# 5_Ethernet.net
KiCad netlist of a schematic drawn in Altium Designer
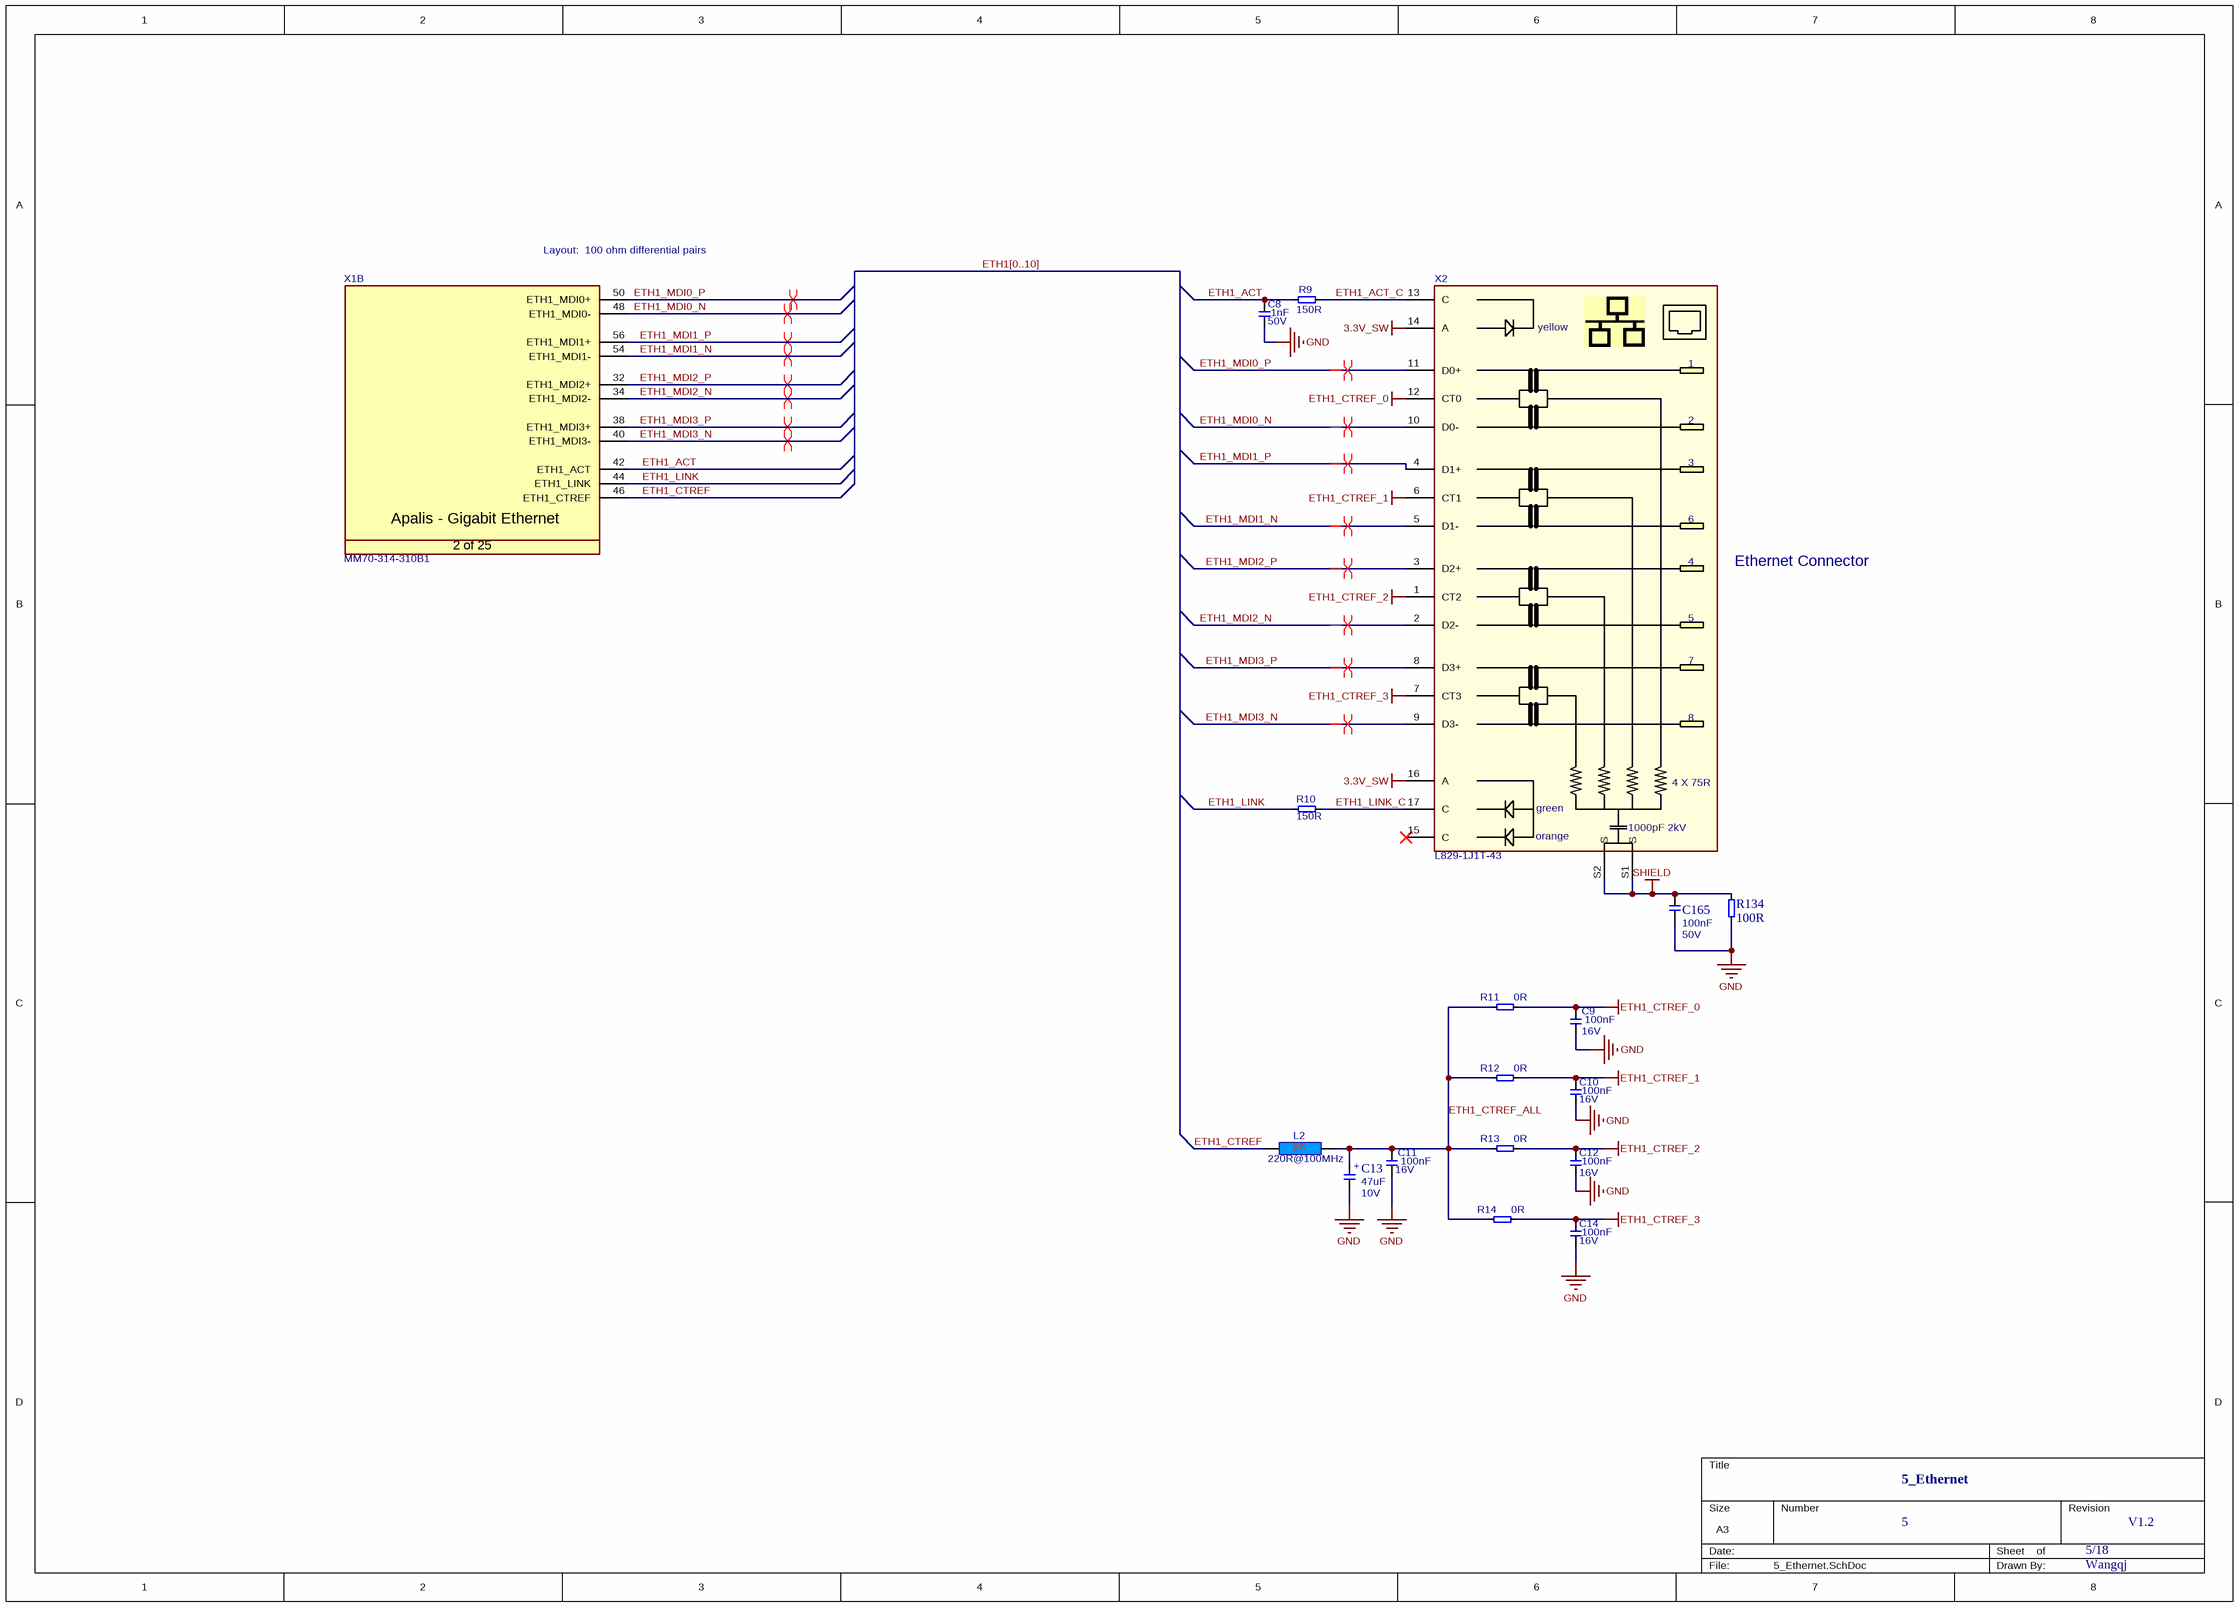
[diagram p0: 5_Ethernet.SchDoc]

(export (version "E")
  (design (tool "Eeschema 10.0.6"))
  (components
    (comp (ref "C8")
      (value "1nF")
      (footprint "CAPC1005X60N")
      (description "Capacitor Ceramic X7R 1nF 50V 10% 0402")
      (fields (field (name "TOLERANCE") "10%") (field (name "RATING") "50V"))
      (libsource (lib "Apalis Evaluation Board") (part "C-X7R-1nF-50V-10%-0402"))
    )
    (comp (ref "C9")
      (value "100nF")
      (footprint "T_CAPC0603X33N")
      (description "Capacitor Ceramic X7R 100nF 16V 10% 0603")
      (fields (field (name "TOLERANCE") "10%") (field (name "RATING") "16V"))
      (libsource (lib "Apalis Evaluation Board") (part "C-X7R-100nF-16V-10%-0603"))
    )
    (comp (ref "C10")
      (value "100nF")
      (footprint "T_CAPC0603X33N")
      (description "Capacitor Ceramic X7R 100nF 16V 10% 0603")
      (fields (field (name "TOLERANCE") "10%") (field (name "RATING") "16V"))
      (libsource (lib "Apalis Evaluation Board") (part "C-X7R-100nF-16V-10%-0603"))
    )
    (comp (ref "C11")
      (value "100nF")
      (footprint "T_CAPC0603X33N")
      (description "Capacitor Ceramic X7R 100nF 16V 10% 0603")
      (fields (field (name "TOLERANCE") "10%") (field (name "RATING") "16V"))
      (libsource (lib "Apalis Evaluation Board") (part "C-X7R-100nF-16V-10%-0603"))
    )
    (comp (ref "C12")
      (value "100nF")
      (footprint "T_CAPC0603X33N")
      (description "Capacitor Ceramic X7R 100nF 16V 10% 0603")
      (fields (field (name "TOLERANCE") "10%") (field (name "RATING") "16V"))
      (libsource (lib "Apalis Evaluation Board") (part "C-X7R-100nF-16V-10%-0603"))
    )
    (comp (ref "C13")
      (value "47uF")
      (footprint "T_CAPMP3216X180N")
      (description "Capacitor TA 47uF 10V 10% 3216")
      (fields (field (name "TOLERANCE") "10%") (field (name "RATING") "10V"))
      (libsource (lib "Apalis Evaluation Board") (part "C-47uF-10V-10%-3216-TA"))
    )
    (comp (ref "C14")
      (value "100nF")
      (footprint "T_CAPC0603X33N")
      (description "Capacitor Ceramic X7R 100nF 16V 10% 0603")
      (fields (field (name "TOLERANCE") "10%") (field (name "RATING") "16V"))
      (libsource (lib "Apalis Evaluation Board") (part "C-X7R-100nF-16V-10%-0603"))
    )
    (comp (ref "C165")
      (value "100nF")
      (footprint "T_CAPC0603X33N")
      (description "Capacitor Ceramic X7R 100nF 50V 20% 0603")
      (fields (field (name "TOLERANCE") "20%") (field (name "RATING") "50V"))
      (libsource (lib "Apalis Evaluation Board") (part "C-100nF-50V-20%-0603-X7R"))
    )
    (comp (ref "L2")
      (value "220R@100MHz")
      (footprint "INDC1608X95N")
      (description "220R@100MHz 2A EMI FILTER")
      (fields (field (name "TOLERANCE") "25%"))
      (libsource (lib "Apalis Evaluation Board") (part "L-220R@100MHz-2A-25%-0603"))
    )
    (comp (ref "R9")
      (value "150R")
      (footprint "t_RESC0603X30N")
      (description "Resistor 150 ohm 63mW 1% 0603")
      (fields (field (name "TOLERANCE") "1%"))
      (libsource (lib "Apalis Evaluation Board") (part "R-150R-63mW-1%-0603"))
    )
    (comp (ref "R10")
      (value "150R")
      (footprint "t_RESC0603X30N")
      (description "Resistor 150 ohm 63mW 1% 0603")
      (fields (field (name "TOLERANCE") "1%"))
      (libsource (lib "Apalis Evaluation Board") (part "R-150R-63mW-1%-0603"))
    )
    (comp (ref "R11")
      (value "0R")
      (footprint "T_RESC0603X30N")
      (description "Resistor 0 ohm 63mW 1% 0603")
      (fields (field (name "TOLERANCE") "1%"))
      (libsource (lib "Apalis Evaluation Board") (part "R-0R-63mW-1%-0603"))
    )
    (comp (ref "R12")
      (value "0R")
      (footprint "T_RESC0603X30N")
      (description "Resistor 0 ohm 63mW 1% 0603")
      (fields (field (name "TOLERANCE") "1%"))
      (libsource (lib "Apalis Evaluation Board") (part "R-0R-63mW-1%-0603"))
    )
    (comp (ref "R13")
      (value "0R")
      (footprint "T_RESC0603X30N")
      (description "Resistor 0 ohm 63mW 1% 0603")
      (fields (field (name "TOLERANCE") "1%"))
      (libsource (lib "Apalis Evaluation Board") (part "R-0R-63mW-1%-0603"))
    )
    (comp (ref "R14")
      (value "0R")
      (footprint "T_RESC0603X30N")
      (description "Resistor 0 ohm 63mW 1% 0603")
      (fields (field (name "TOLERANCE") "1%"))
      (libsource (lib "Apalis Evaluation Board") (part "R-0R-63mW-1%-0603"))
    )
    (comp (ref "R134")
      (value "100R")
      (footprint "T_RESC0603X30N")
      (description "Resistor 120 ohm 63mW 5% 0603")
      (fields (field (name "TOLERANCE") "5%"))
      (libsource (lib "Apalis Evaluation Board") (part "R-120R-63mW-5%-0603"))
    )
    (comp (ref "X1")
      (value "CON-JAE-MM70-314-310B1-314-0.5mm")
      (footprint "T_JAE_MM70-314-310B1")
      (description "MXM3 Connector")
      (fields (field (name "MANUFACTURER PART NO.") "MM70-314-310B1"))
      (libsource (lib "Apalis Evaluation Board") (part "CON-JAE-MM70-314-310B1-314-0.5mm"))
    )
    (comp (ref "X2")
      (value "L829-1J1T-43")
      (footprint "T_BEL_L829-1J1T-43")
      (description "Low profile 10/100/1G Mag Jack")
      (fields (field (name "MANUFACTURER PART NO.") "L829-1J1T-43"))
      (libsource (lib "Apalis Evaluation Board") (part "CON-BEL-L829-1J1T-43"))
    )
  )
  (nets
    (net (code "13") (name "/ETH1_ACT") (class "Default")
      (node (ref "C8") (pin "2") (pinfunction "2_2") (pintype "passive"))
      (node (ref "R9") (pin "1") (pinfunction "1_1") (pintype "passive"))
      (node (ref "X1") (pin "42") (pinfunction "ETH1_ACT_42") (pintype "passive"))
    )
    (net (code "14") (name "/ETH1_ACT_C") (class "Default")
      (node (ref "R9") (pin "2") (pinfunction "2_2") (pintype "passive"))
      (node (ref "X2") (pin "13") (pinfunction "C_13") (pintype "passive"))
    )
    (net (code "15") (name "/ETH1_CTREF") (class "Default")
      (node (ref "L2") (pin "1") (pinfunction "1_1") (pintype "passive"))
      (node (ref "X1") (pin "46") (pinfunction "ETH1_CTREF_46") (pintype "passive"))
    )
    (net (code "16") (name "/ETH1_CTREF_ALL") (class "Default")
      (node (ref "C11") (pin "2") (pinfunction "2_2") (pintype "passive"))
      (node (ref "C13") (pin "1") (pinfunction "1_1") (pintype "passive"))
      (node (ref "L2") (pin "2") (pinfunction "2_2") (pintype "passive"))
      (node (ref "R11") (pin "1") (pinfunction "1_1") (pintype "passive"))
      (node (ref "R12") (pin "1") (pinfunction "1_1") (pintype "passive"))
      (node (ref "R13") (pin "1") (pinfunction "1_1") (pintype "passive"))
      (node (ref "R14") (pin "1") (pinfunction "1_1") (pintype "passive"))
    )
    (net (code "17") (name "/ETH1_LINK") (class "Default")
      (node (ref "R10") (pin "1") (pinfunction "1_1") (pintype "passive"))
      (node (ref "X1") (pin "44") (pinfunction "ETH1_LINK_44") (pintype "passive"))
    )
    (net (code "18") (name "/ETH1_LINK_C") (class "Default")
      (node (ref "R10") (pin "2") (pinfunction "2_2") (pintype "passive"))
      (node (ref "X2") (pin "17") (pinfunction "C_17") (pintype "passive"))
    )
    (net (code "19") (name "/ETH1_MDI0_N") (class "Default")
      (node (ref "X1") (pin "48") (pinfunction "ETH1_MDI0-_48") (pintype "passive"))
      (node (ref "X2") (pin "10") (pinfunction "D0-_10") (pintype "passive"))
    )
    (net (code "20") (name "/ETH1_MDI0_P") (class "Default")
      (node (ref "X1") (pin "50") (pinfunction "ETH1_MDI0+_50") (pintype "passive"))
      (node (ref "X2") (pin "11") (pinfunction "D0+_11") (pintype "passive"))
    )
    (net (code "21") (name "/ETH1_MDI1_N") (class "Default")
      (node (ref "X1") (pin "54") (pinfunction "ETH1_MDI1-_54") (pintype "passive"))
      (node (ref "X2") (pin "5") (pinfunction "D1-_5") (pintype "passive"))
    )
    (net (code "22") (name "/ETH1_MDI1_P") (class "Default")
      (node (ref "X1") (pin "56") (pinfunction "ETH1_MDI1+_56") (pintype "passive"))
      (node (ref "X2") (pin "4") (pinfunction "D1+_4") (pintype "passive"))
    )
    (net (code "23") (name "/ETH1_MDI2_N") (class "Default")
      (node (ref "X1") (pin "34") (pinfunction "ETH1_MDI2-_34") (pintype "passive"))
      (node (ref "X2") (pin "2") (pinfunction "D2-_2") (pintype "passive"))
    )
    (net (code "24") (name "/ETH1_MDI2_P") (class "Default")
      (node (ref "X1") (pin "32") (pinfunction "ETH1_MDI2+_32") (pintype "passive"))
      (node (ref "X2") (pin "3") (pinfunction "D2+_3") (pintype "passive"))
    )
    (net (code "25") (name "/ETH1_MDI3_N") (class "Default")
      (node (ref "X1") (pin "40") (pinfunction "ETH1_MDI3-_40") (pintype "passive"))
      (node (ref "X2") (pin "9") (pinfunction "D3-_9") (pintype "passive"))
    )
    (net (code "26") (name "/ETH1_MDI3_P") (class "Default")
      (node (ref "X1") (pin "38") (pinfunction "ETH1_MDI3+_38") (pintype "passive"))
      (node (ref "X2") (pin "8") (pinfunction "D3+_8") (pintype "passive"))
    )
    (net (code "27") (name "3.3V_SW") (class "Default")
      (node (ref "X2") (pin "14") (pinfunction "A_14") (pintype "passive"))
      (node (ref "X2") (pin "16") (pinfunction "A_16") (pintype "passive"))
    )
    (net (code "28") (name "ETH1_CTREF_0") (class "Default")
      (node (ref "C9") (pin "2") (pinfunction "2_2") (pintype "passive"))
      (node (ref "R11") (pin "2") (pinfunction "2_2") (pintype "passive"))
      (node (ref "X2") (pin "12") (pinfunction "CT0_12") (pintype "passive"))
    )
    (net (code "29") (name "ETH1_CTREF_1") (class "Default")
      (node (ref "C10") (pin "2") (pinfunction "2_2") (pintype "passive"))
      (node (ref "R12") (pin "2") (pinfunction "2_2") (pintype "passive"))
      (node (ref "X2") (pin "6") (pinfunction "CT1_6") (pintype "passive"))
    )
    (net (code "30") (name "ETH1_CTREF_2") (class "Default")
      (node (ref "C12") (pin "2") (pinfunction "2_2") (pintype "passive"))
      (node (ref "R13") (pin "2") (pinfunction "2_2") (pintype "passive"))
      (node (ref "X2") (pin "1") (pinfunction "CT2_1") (pintype "passive"))
    )
    (net (code "31") (name "ETH1_CTREF_3") (class "Default")
      (node (ref "C14") (pin "2") (pinfunction "2_2") (pintype "passive"))
      (node (ref "R14") (pin "2") (pinfunction "2_2") (pintype "passive"))
      (node (ref "X2") (pin "7") (pinfunction "CT3_7") (pintype "passive"))
    )
    (net (code "32") (name "GND") (class "Default")
      (node (ref "C10") (pin "1") (pinfunction "1_1") (pintype "passive"))
      (node (ref "C11") (pin "1") (pinfunction "1_1") (pintype "passive"))
      (node (ref "C12") (pin "1") (pinfunction "1_1") (pintype "passive"))
      (node (ref "C13") (pin "2") (pinfunction "2_2") (pintype "passive"))
      (node (ref "C14") (pin "1") (pinfunction "1_1") (pintype "passive"))
      (node (ref "C165") (pin "1") (pinfunction "1_1") (pintype "passive"))
      (node (ref "C8") (pin "1") (pinfunction "1_1") (pintype "passive"))
      (node (ref "C9") (pin "1") (pinfunction "1_1") (pintype "passive"))
      (node (ref "R134") (pin "1") (pinfunction "1_1") (pintype "passive"))
    )
    (net (code "33") (name "SHIELD") (class "Default")
      (node (ref "C165") (pin "2") (pinfunction "2_2") (pintype "passive"))
      (node (ref "R134") (pin "2") (pinfunction "2_2") (pintype "passive"))
      (node (ref "X2") (pin "S1") (pinfunction "S_S1") (pintype "passive"))
      (node (ref "X2") (pin "S2") (pinfunction "S_S2") (pintype "passive"))
    )
    (net (code "34") (name "unconnected-(X2-C-Pad15)") (class "Default")
      (node (ref "X2") (pin "15") (pinfunction "C_15") (pintype "passive+no_connect"))
    )
  )
)
